# poiduino7.net
KiCad netlist of a schematic drawn in EAGLE
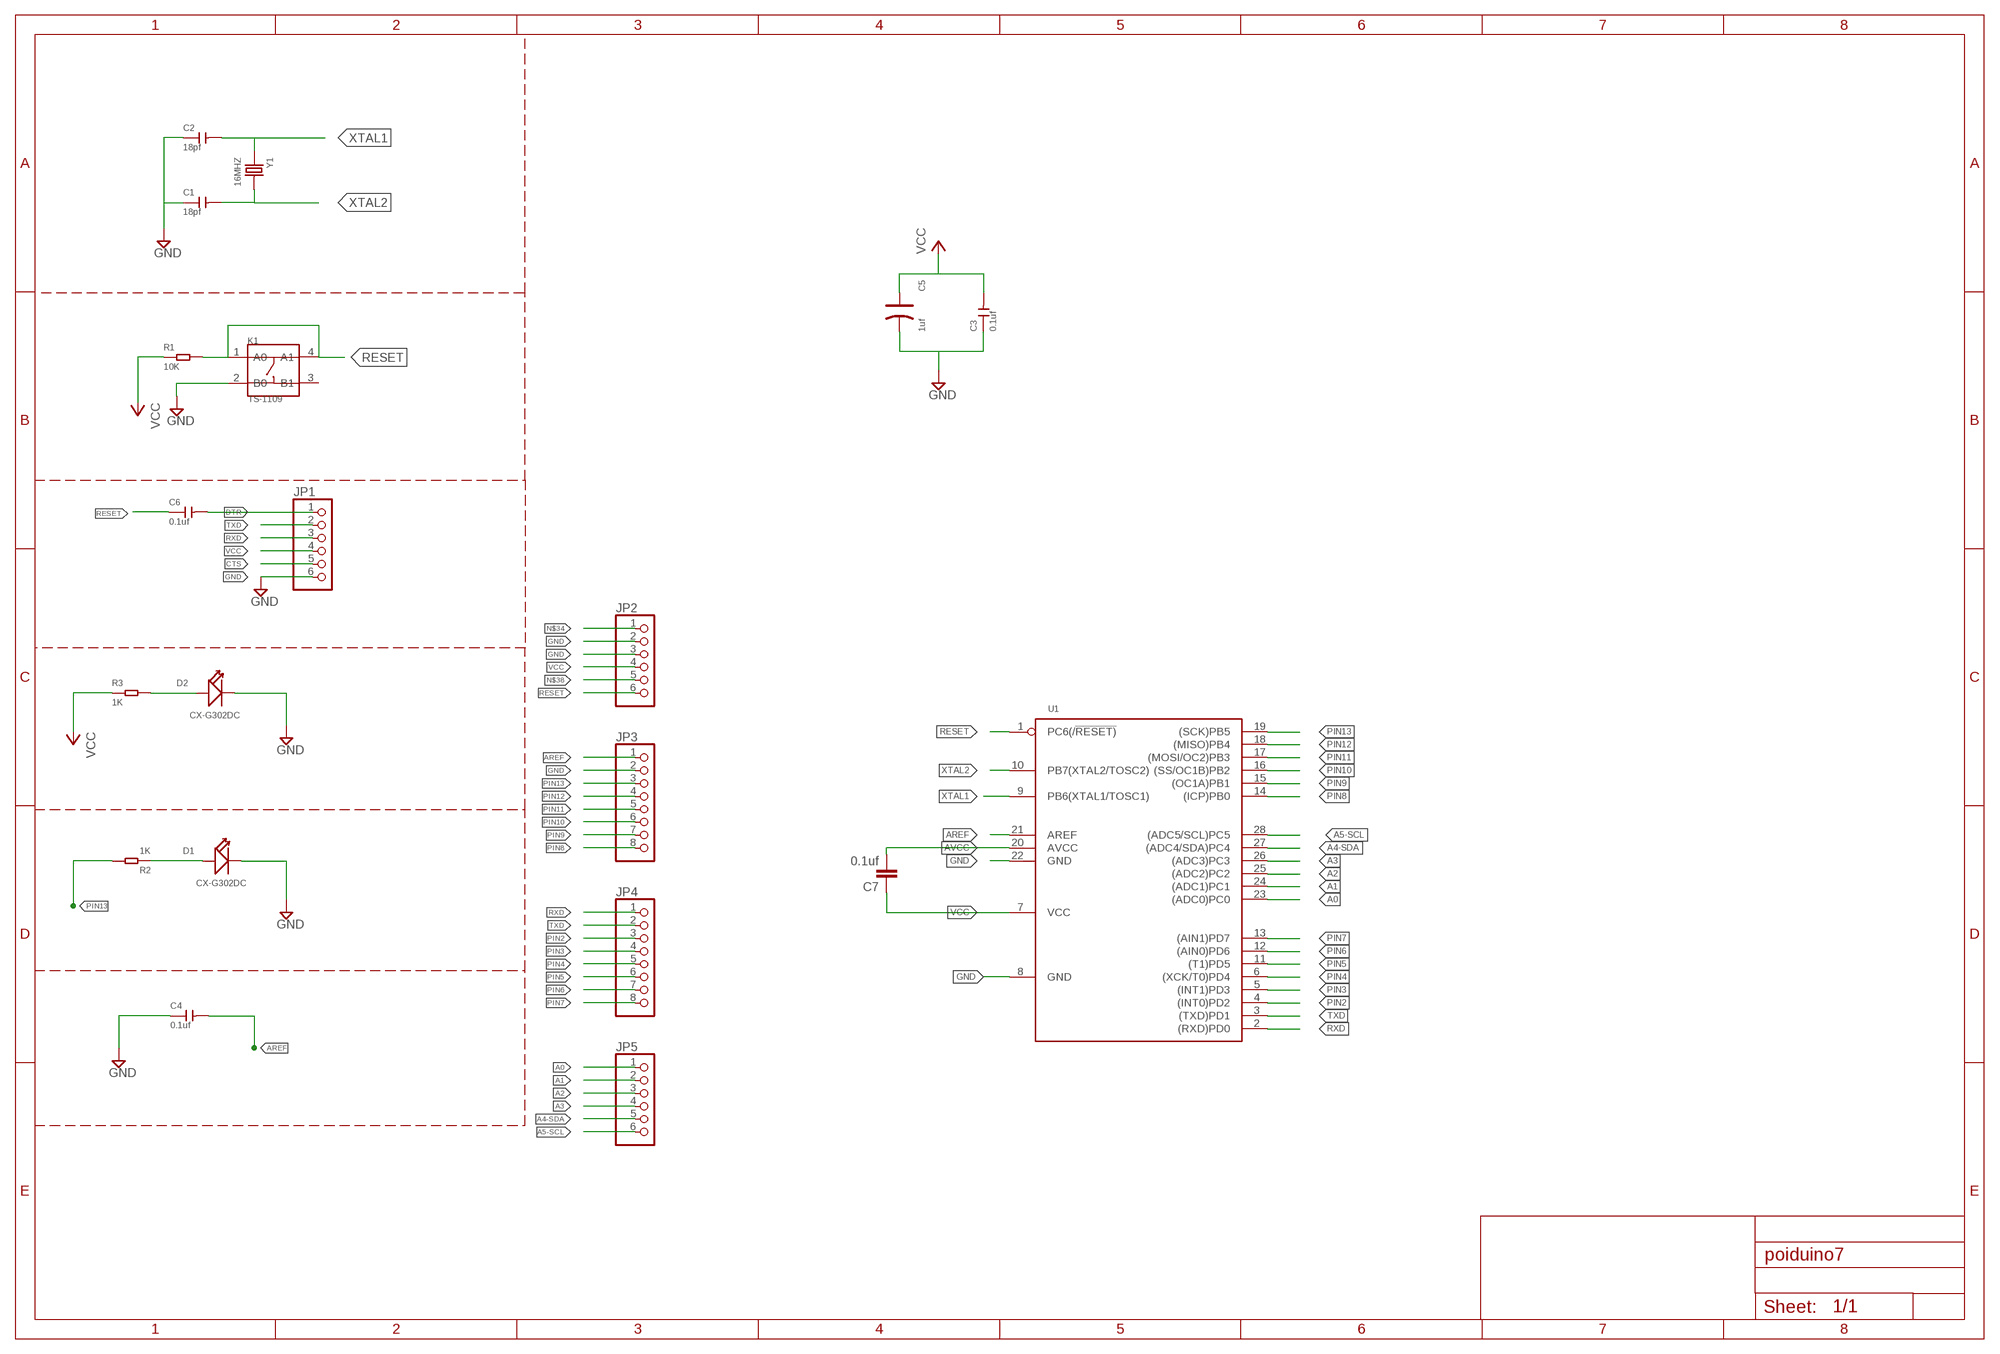
[diagram p0: schematic, sheet 1]

(export (version "E")
  (design (tool "Eeschema 10.0.6"))
  (components
    (comp (ref "C1")
      (value "18pf")
      (footprint "eagle-import:CERAMIC-2.54")
      (libsource (lib "eagle-import") (part "DIP-CERAMIC-DISC-10NF-50V-Y5V(D4.0MM)"))
    )
    (comp (ref "C2")
      (value "18pf")
      (footprint "eagle-import:CERAMIC-2.54")
      (libsource (lib "eagle-import") (part "DIP-CERAMIC-DISC-10NF-50V-Y5V(D4.0MM)"))
    )
    (comp (ref "C3")
      (value "0.1uf")
      (footprint "eagle-import:CERAMIC-2.54")
      (libsource (lib "eagle-import") (part "DIP-CERAMIC-DISC-10NF-50V-Y5V(D4.0MM)"))
    )
    (comp (ref "C4")
      (value "0.1uf")
      (footprint "eagle-import:CERAMIC-2.54")
      (libsource (lib "eagle-import") (part "DIP-CERAMIC-DISC-10NF-50V-Y5V(D4.0MM)"))
    )
    (comp (ref "C5")
      (value "1uf")
      (footprint "eagle-import:PC-D5.3MM")
      (fields (field (name "MPN") "KS 100uF/16V"))
      (libsource (lib "eagle-import") (part "DIP-ALUMINUM-47UF-16V(D5-H7MM)"))
    )
    (comp (ref "C6")
      (value "0.1uf")
      (footprint "eagle-import:CERAMIC-2.54")
      (libsource (lib "eagle-import") (part "DIP-CERAMIC-DISC-10NF-50V-Y5V(D4.0MM)"))
    )
    (comp (ref "C7")
      (value "0.1uf")
      (footprint "eagle-import:C5B2.5")
      (libsource (lib "eagle-import") (part "C5/2.5"))
    )
    (comp (ref "D1")
      (value "CX-G302DC")
      (footprint "eagle-import:LED2-2.54-D3.0MM")
      (libsource (lib "eagle-import") (part "DIP-LED-GREEN-GREEN(2P-D3MM)"))
    )
    (comp (ref "D2")
      (value "CX-G302DC")
      (footprint "eagle-import:LED2-2.54-D3.0MM")
      (libsource (lib "eagle-import") (part "DIP-LED-GREEN-GREEN(2P-D3MM)"))
    )
    (comp (ref "JP1")
      (value "PINHD-1X6")
      (footprint "eagle-import:1X06")
      (libsource (lib "eagle-import") (part "PINHD-1X6"))
    )
    (comp (ref "JP2")
      (value "PINHD-1X6")
      (footprint "eagle-import:1X06")
      (libsource (lib "eagle-import") (part "PINHD-1X6"))
    )
    (comp (ref "JP3")
      (value "PINHD-1X8")
      (footprint "eagle-import:1X08")
      (libsource (lib "eagle-import") (part "PINHD-1X8"))
    )
    (comp (ref "JP4")
      (value "PINHD-1X8")
      (footprint "eagle-import:1X08")
      (libsource (lib "eagle-import") (part "PINHD-1X8"))
    )
    (comp (ref "JP5")
      (value "PINHD-1X6")
      (footprint "eagle-import:1X06")
      (libsource (lib "eagle-import") (part "PINHD-1X6"))
    )
    (comp (ref "K1")
      (value "TS-1109")
      (footprint "eagle-import:SW4-6.0X6.0X5.0MM")
      (libsource (lib "eagle-import") (part "DIP-BUTTON-4P"))
    )
    (comp (ref "R1")
      (value "10K")
      (footprint "eagle-import:PR-D2.3XL6.5MM")
      (fields (field (name "MPN") "FHCFR-1/4W-103J"))
      (libsource (lib "eagle-import") (part "DIP-RES-10K-5%-1/4W(PR-D2.3XL6.5MM)"))
    )
    (comp (ref "R2")
      (value "1K")
      (footprint "eagle-import:PR-D2.3XL6.5MM")
      (fields (field (name "MPN") "FHCFR-1/4W-102J"))
      (libsource (lib "eagle-import") (part "DIP-RES-1K-5%-1/4W(PR-D2.3XL6.5MM)"))
    )
    (comp (ref "R3")
      (value "1K")
      (footprint "eagle-import:PR-D2.3XL6.5MM")
      (fields (field (name "MPN") "FHCFR-1/4W-102J"))
      (libsource (lib "eagle-import") (part "DIP-RES-1K-5%-1/4W(PR-D2.3XL6.5MM)"))
    )
    (comp (ref "U1")
      (value "MCU-ATMEGA328P-PU(DIP28)")
      (footprint "eagle-import:DIP28-2.54-34.7X7.62MM")
      (fields (field (name "MPN") "ATMEGA328P-PU"))
      (libsource (lib "eagle-import") (part "MCU-ATMEGA328P-PU(DIP28)"))
    )
    (comp (ref "Y1")
      (value "16MHZ")
      (footprint "eagle-import:HC49US")
      (fields (field (name "MPN") "HC-49US    16.000MHz"))
      (libsource (lib "eagle-import") (part "DIP-CRYSTAL-16MHZ-18PF-30PPM-40R(HC49US)"))
    )
  )
  (nets
    (net (code "1") (name "A0") (class "Default")
      (node (ref "JP5") (pin "1") (pinfunction "1_1") (pintype "passive"))
      (node (ref "U1") (pin "23") (pinfunction "(ADC0)PC0_23") (pintype "bidirectional"))
    )
    (net (code "2") (name "A1") (class "Default")
      (node (ref "JP5") (pin "2") (pinfunction "2_2") (pintype "passive"))
      (node (ref "U1") (pin "24") (pinfunction "(ADC1)PC1_24") (pintype "bidirectional"))
    )
    (net (code "3") (name "A2") (class "Default")
      (node (ref "JP5") (pin "3") (pinfunction "3_3") (pintype "passive"))
      (node (ref "U1") (pin "25") (pinfunction "(ADC2)PC2_25") (pintype "bidirectional"))
    )
    (net (code "4") (name "A3") (class "Default")
      (node (ref "JP5") (pin "4") (pinfunction "4_4") (pintype "passive"))
      (node (ref "U1") (pin "26") (pinfunction "(ADC3)PC3_26") (pintype "bidirectional"))
    )
    (net (code "5") (name "A4-SDA") (class "Default")
      (node (ref "JP5") (pin "5") (pinfunction "5_5") (pintype "passive"))
      (node (ref "U1") (pin "27") (pinfunction "(ADC4/SDA)PC4_27") (pintype "bidirectional"))
    )
    (net (code "6") (name "A5-SCL") (class "Default")
      (node (ref "JP5") (pin "6") (pinfunction "6_6") (pintype "passive"))
      (node (ref "U1") (pin "28") (pinfunction "(ADC5/SCL)PC5_28") (pintype "bidirectional"))
    )
    (net (code "7") (name "AREF") (class "Default")
      (node (ref "C4") (pin "2") (pinfunction "2_2") (pintype "passive"))
      (node (ref "JP3") (pin "1") (pinfunction "1_1") (pintype "passive"))
      (node (ref "U1") (pin "21") (pinfunction "AREF_21") (pintype "bidirectional"))
    )
    (net (code "8") (name "AVCC") (class "Default")
      (node (ref "C7") (pin "2") (pinfunction "2_2") (pintype "passive"))
      (node (ref "U1") (pin "20") (pinfunction "AVCC_20") (pintype "bidirectional"))
    )
    (net (code "9") (name "CTS") (class "Default")
      (node (ref "JP1") (pin "5") (pinfunction "5_5") (pintype "passive"))
    )
    (net (code "10") (name "DTR") (class "Default")
      (node (ref "C6") (pin "2") (pinfunction "2_2") (pintype "passive"))
      (node (ref "JP1") (pin "1") (pinfunction "1_1") (pintype "passive"))
    )
    (net (code "11") (name "GND") (class "Default")
      (node (ref "C1") (pin "1") (pinfunction "1_1") (pintype "passive"))
      (node (ref "C2") (pin "1") (pinfunction "1_1") (pintype "passive"))
      (node (ref "C3") (pin "1") (pinfunction "1_1") (pintype "passive"))
      (node (ref "C4") (pin "1") (pinfunction "1_1") (pintype "passive"))
      (node (ref "C5") (pin "-") (pinfunction "-_-") (pintype "passive"))
      (node (ref "D1") (pin "K") (pinfunction "-_K") (pintype "passive"))
      (node (ref "D2") (pin "K") (pinfunction "-_K") (pintype "passive"))
      (node (ref "JP1") (pin "6") (pinfunction "6_6") (pintype "passive"))
      (node (ref "JP2") (pin "2") (pinfunction "2_2") (pintype "passive"))
      (node (ref "JP2") (pin "3") (pinfunction "3_3") (pintype "passive"))
      (node (ref "JP3") (pin "2") (pinfunction "2_2") (pintype "passive"))
      (node (ref "K1") (pin "2") (pinfunction "B0_2") (pintype "bidirectional"))
      (node (ref "U1") (pin "22") (pinfunction "GND_22") (pintype "bidirectional"))
      (node (ref "U1") (pin "8") (pinfunction "GND_8") (pintype "bidirectional"))
    )
    (net (code "12") (name "N$34") (class "Default")
      (node (ref "JP2") (pin "1") (pinfunction "1_1") (pintype "passive"))
    )
    (net (code "13") (name "N$38") (class "Default")
      (node (ref "JP2") (pin "5") (pinfunction "5_5") (pintype "passive"))
    )
    (net (code "14") (name "Net-(D1-+)") (class "Default")
      (node (ref "D1") (pin "A") (pinfunction "+_A") (pintype "passive"))
      (node (ref "R2") (pin "1") (pinfunction "1_1") (pintype "passive"))
    )
    (net (code "15") (name "Net-(D2-+)") (class "Default")
      (node (ref "D2") (pin "A") (pinfunction "+_A") (pintype "passive"))
      (node (ref "R3") (pin "2") (pinfunction "2_2") (pintype "passive"))
    )
    (net (code "16") (name "PIN2") (class "Default")
      (node (ref "JP4") (pin "3") (pinfunction "3_3") (pintype "passive"))
      (node (ref "U1") (pin "4") (pinfunction "(INT0)PD2_4") (pintype "bidirectional"))
    )
    (net (code "17") (name "PIN3") (class "Default")
      (node (ref "JP4") (pin "4") (pinfunction "4_4") (pintype "passive"))
      (node (ref "U1") (pin "5") (pinfunction "(INT1)PD3_5") (pintype "bidirectional"))
    )
    (net (code "18") (name "PIN4") (class "Default")
      (node (ref "JP4") (pin "5") (pinfunction "5_5") (pintype "passive"))
      (node (ref "U1") (pin "6") (pinfunction "(XCK/T0)PD4_6") (pintype "bidirectional"))
    )
    (net (code "19") (name "PIN5") (class "Default")
      (node (ref "JP4") (pin "6") (pinfunction "6_6") (pintype "passive"))
      (node (ref "U1") (pin "11") (pinfunction "(T1)PD5_11") (pintype "bidirectional"))
    )
    (net (code "20") (name "PIN6") (class "Default")
      (node (ref "JP4") (pin "7") (pinfunction "7_7") (pintype "passive"))
      (node (ref "U1") (pin "12") (pinfunction "(AIN0)PD6_12") (pintype "bidirectional"))
    )
    (net (code "21") (name "PIN7") (class "Default")
      (node (ref "JP4") (pin "8") (pinfunction "8_8") (pintype "passive"))
      (node (ref "U1") (pin "13") (pinfunction "(AIN1)PD7_13") (pintype "bidirectional"))
    )
    (net (code "22") (name "PIN8") (class "Default")
      (node (ref "JP3") (pin "8") (pinfunction "8_8") (pintype "passive"))
      (node (ref "U1") (pin "14") (pinfunction "(ICP)PB0_14") (pintype "bidirectional"))
    )
    (net (code "23") (name "PIN9") (class "Default")
      (node (ref "JP3") (pin "7") (pinfunction "7_7") (pintype "passive"))
      (node (ref "U1") (pin "15") (pinfunction "(OC1A)PB1_15") (pintype "bidirectional"))
    )
    (net (code "24") (name "PIN10") (class "Default")
      (node (ref "JP3") (pin "6") (pinfunction "6_6") (pintype "passive"))
      (node (ref "U1") (pin "16") (pinfunction "(SS/OC1B)PB2_16") (pintype "bidirectional"))
    )
    (net (code "25") (name "PIN11") (class "Default")
      (node (ref "JP3") (pin "5") (pinfunction "5_5") (pintype "passive"))
      (node (ref "U1") (pin "17") (pinfunction "(MOSI/OC2)PB3_17") (pintype "bidirectional"))
    )
    (net (code "26") (name "PIN12") (class "Default")
      (node (ref "JP3") (pin "4") (pinfunction "4_4") (pintype "passive"))
      (node (ref "U1") (pin "18") (pinfunction "(MISO)PB4_18") (pintype "bidirectional"))
    )
    (net (code "27") (name "PIN13") (class "Default")
      (node (ref "JP3") (pin "3") (pinfunction "3_3") (pintype "passive"))
      (node (ref "R2") (pin "2") (pinfunction "2_2") (pintype "passive"))
      (node (ref "U1") (pin "19") (pinfunction "(SCK)PB5_19") (pintype "bidirectional"))
    )
    (net (code "28") (name "RESET") (class "Default")
      (node (ref "C6") (pin "1") (pinfunction "1_1") (pintype "passive"))
      (node (ref "JP2") (pin "6") (pinfunction "6_6") (pintype "passive"))
      (node (ref "K1") (pin "1") (pinfunction "A0_1") (pintype "bidirectional"))
      (node (ref "K1") (pin "4") (pinfunction "A1_4") (pintype "bidirectional"))
      (node (ref "R1") (pin "2") (pinfunction "2_2") (pintype "passive"))
      (node (ref "U1") (pin "1") (pinfunction "PC6(/~{RESET})_1") (pintype "bidirectional"))
    )
    (net (code "29") (name "RXD") (class "Default")
      (node (ref "JP1") (pin "3") (pinfunction "3_3") (pintype "passive"))
      (node (ref "JP4") (pin "1") (pinfunction "1_1") (pintype "passive"))
      (node (ref "U1") (pin "2") (pinfunction "(RXD)PD0_2") (pintype "bidirectional"))
    )
    (net (code "30") (name "TXD") (class "Default")
      (node (ref "JP1") (pin "2") (pinfunction "2_2") (pintype "passive"))
      (node (ref "JP4") (pin "2") (pinfunction "2_2") (pintype "passive"))
      (node (ref "U1") (pin "3") (pinfunction "(TXD)PD1_3") (pintype "bidirectional"))
    )
    (net (code "31") (name "VCC") (class "Default")
      (node (ref "C3") (pin "2") (pinfunction "2_2") (pintype "passive"))
      (node (ref "C5") (pin "+") (pinfunction "+_+") (pintype "passive"))
      (node (ref "C7") (pin "1") (pinfunction "1_1") (pintype "passive"))
      (node (ref "JP1") (pin "4") (pinfunction "4_4") (pintype "passive"))
      (node (ref "JP2") (pin "4") (pinfunction "4_4") (pintype "passive"))
      (node (ref "R1") (pin "1") (pinfunction "1_1") (pintype "passive"))
      (node (ref "R3") (pin "1") (pinfunction "1_1") (pintype "passive"))
      (node (ref "U1") (pin "7") (pinfunction "VCC_7") (pintype "bidirectional"))
    )
    (net (code "32") (name "XTAL1") (class "Default")
      (node (ref "C2") (pin "2") (pinfunction "2_2") (pintype "passive"))
      (node (ref "U1") (pin "9") (pinfunction "PB6(XTAL1/TOSC1)_9") (pintype "bidirectional"))
      (node (ref "Y1") (pin "1") (pinfunction "1_1") (pintype "passive"))
    )
    (net (code "33") (name "XTAL2") (class "Default")
      (node (ref "C1") (pin "2") (pinfunction "2_2") (pintype "passive"))
      (node (ref "U1") (pin "10") (pinfunction "PB7(XTAL2/TOSC2)_10") (pintype "bidirectional"))
      (node (ref "Y1") (pin "2") (pinfunction "2_2") (pintype "passive"))
    )
    (net (code "34") (name "unconnected-(K1-B1-Pad3)") (class "Default")
      (node (ref "K1") (pin "3") (pinfunction "B1_3") (pintype "bidirectional"))
    )
  )
)
